# EN715_ExpansionBoard_ver1_2.net
KiCad netlist of a schematic drawn in EAGLE
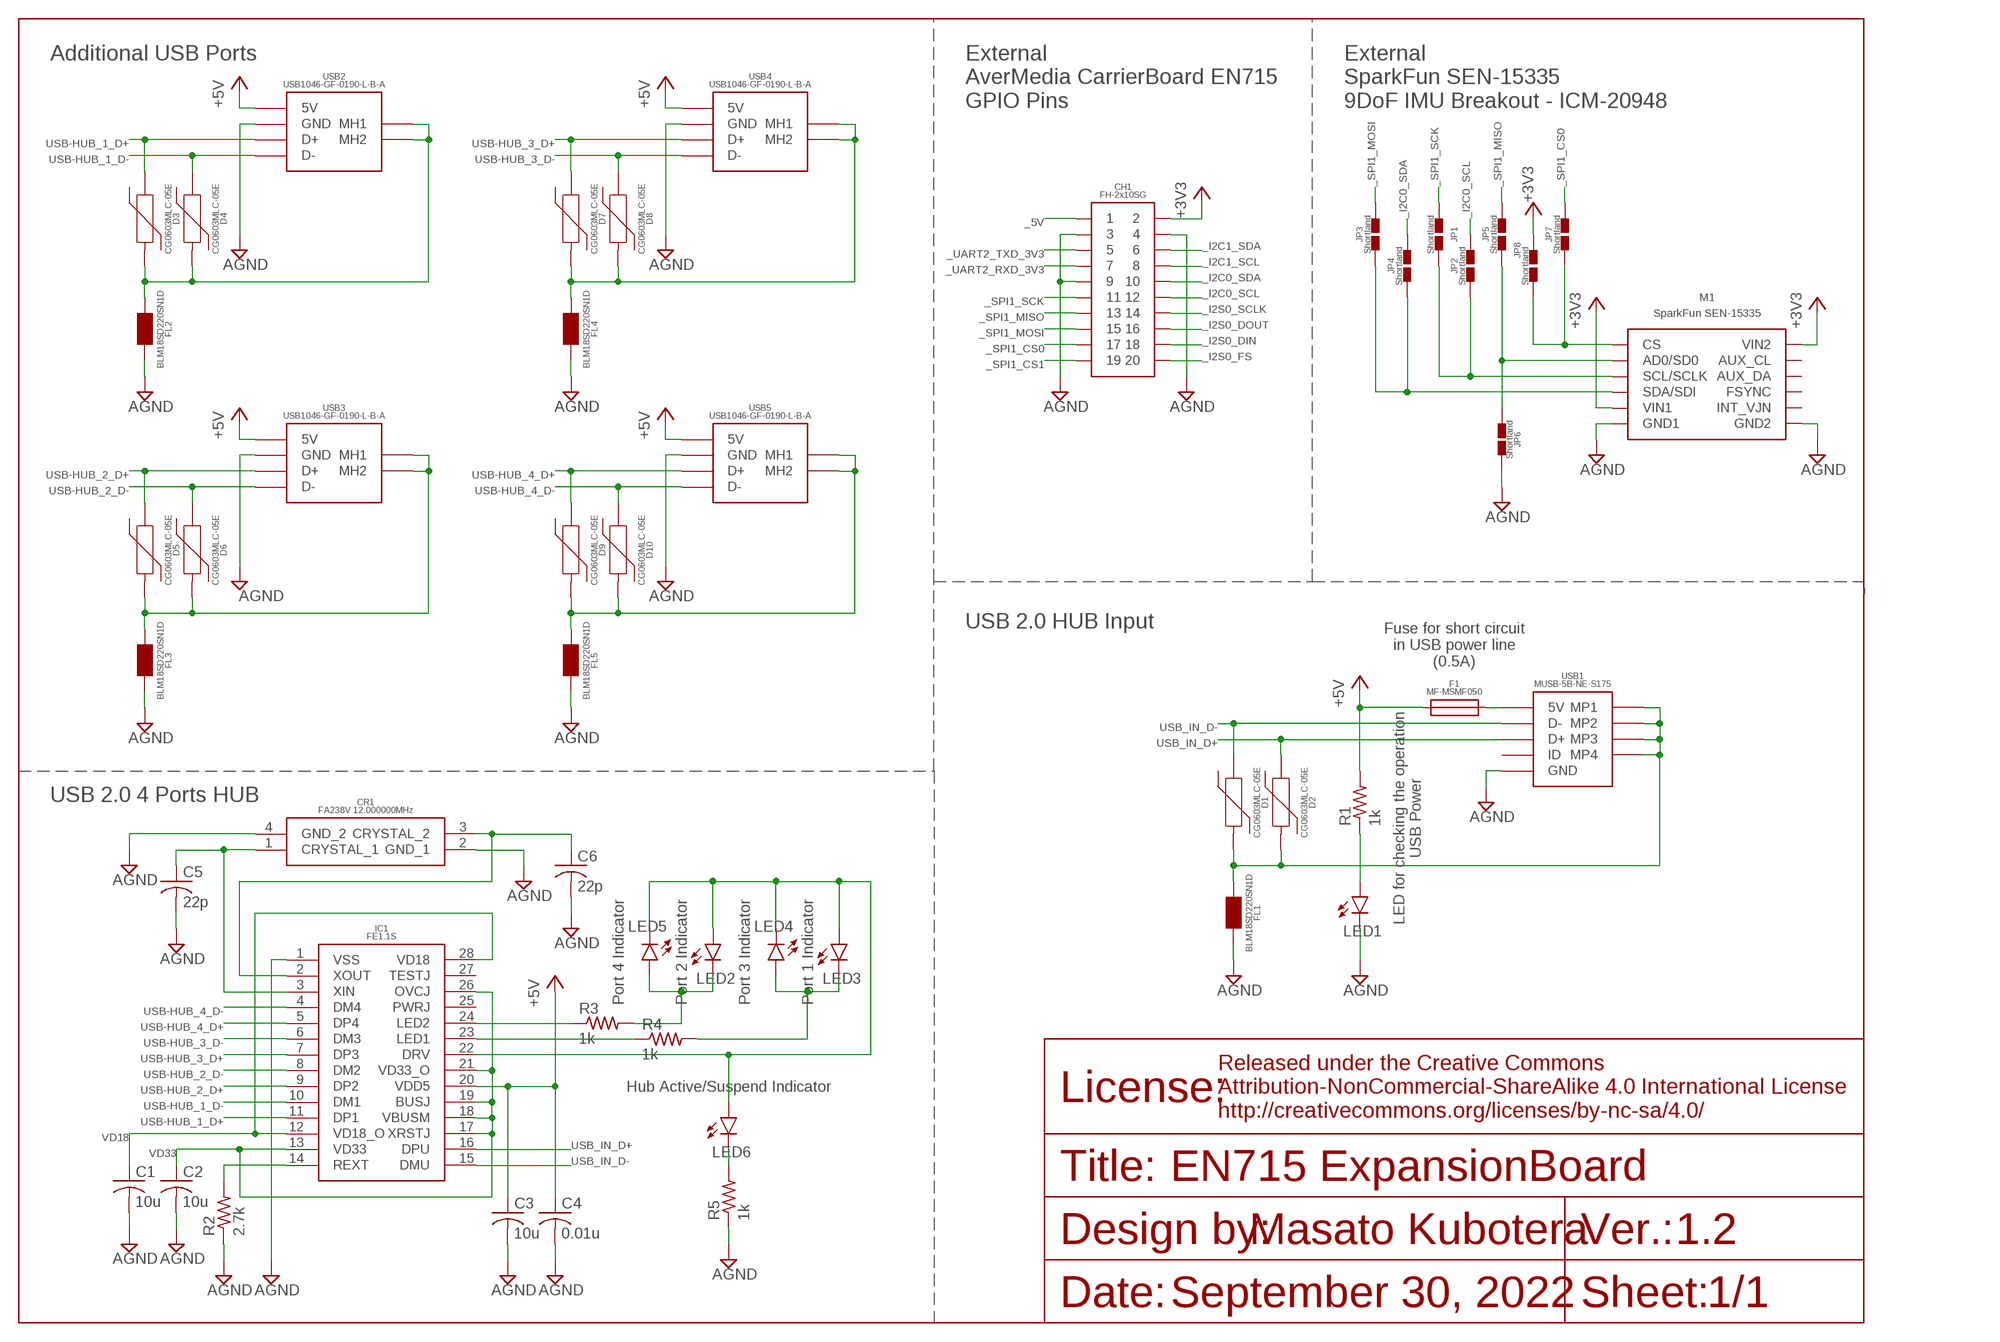
[diagram p0: schematic, sheet 1]

(export (version "E")
  (design (tool "Eeschema 10.0.6"))
  (components
    (comp (ref "C1")
      (value "10u")
      (footprint "eagle-import:C0603")
      (libsource (lib "eagle-import") (part "C-USC0603"))
    )
    (comp (ref "C2")
      (value "10u")
      (footprint "eagle-import:C0603")
      (libsource (lib "eagle-import") (part "C-USC0603"))
    )
    (comp (ref "C3")
      (value "10u")
      (footprint "eagle-import:C0603")
      (libsource (lib "eagle-import") (part "C-USC0603"))
    )
    (comp (ref "C4")
      (value "0.01u")
      (footprint "eagle-import:C0603")
      (libsource (lib "eagle-import") (part "C-USC0603"))
    )
    (comp (ref "C5")
      (value "22p")
      (footprint "eagle-import:C0603")
      (libsource (lib "eagle-import") (part "C-USC0603"))
    )
    (comp (ref "C6")
      (value "22p")
      (footprint "eagle-import:C0603")
      (libsource (lib "eagle-import") (part "C-USC0603"))
    )
    (comp (ref "CH1")
      (value "2X10")
      (footprint "eagle-import:2X10")
      (libsource (lib "eagle-import") (part "2X10"))
    )
    (comp (ref "CR1")
      (value "FA238V_12.000000MHZ")
      (footprint "eagle-import:FA238V")
      (libsource (lib "eagle-import") (part "FA238V_12.000000MHZ"))
    )
    (comp (ref "D1")
      (value "CG0603MLC-05E")
      (footprint "eagle-import:CG0603MLC-05E")
      (libsource (lib "eagle-import") (part "CG0603MLC-05E"))
    )
    (comp (ref "D2")
      (value "CG0603MLC-05E")
      (footprint "eagle-import:CG0603MLC-05E")
      (libsource (lib "eagle-import") (part "CG0603MLC-05E"))
    )
    (comp (ref "D3")
      (value "CG0603MLC-05E")
      (footprint "eagle-import:CG0603MLC-05E")
      (libsource (lib "eagle-import") (part "CG0603MLC-05E"))
    )
    (comp (ref "D4")
      (value "CG0603MLC-05E")
      (footprint "eagle-import:CG0603MLC-05E")
      (libsource (lib "eagle-import") (part "CG0603MLC-05E"))
    )
    (comp (ref "D5")
      (value "CG0603MLC-05E")
      (footprint "eagle-import:CG0603MLC-05E")
      (libsource (lib "eagle-import") (part "CG0603MLC-05E"))
    )
    (comp (ref "D6")
      (value "CG0603MLC-05E")
      (footprint "eagle-import:CG0603MLC-05E")
      (libsource (lib "eagle-import") (part "CG0603MLC-05E"))
    )
    (comp (ref "D7")
      (value "CG0603MLC-05E")
      (footprint "eagle-import:CG0603MLC-05E")
      (libsource (lib "eagle-import") (part "CG0603MLC-05E"))
    )
    (comp (ref "D8")
      (value "CG0603MLC-05E")
      (footprint "eagle-import:CG0603MLC-05E")
      (libsource (lib "eagle-import") (part "CG0603MLC-05E"))
    )
    (comp (ref "D9")
      (value "CG0603MLC-05E")
      (footprint "eagle-import:CG0603MLC-05E")
      (libsource (lib "eagle-import") (part "CG0603MLC-05E"))
    )
    (comp (ref "D10")
      (value "CG0603MLC-05E")
      (footprint "eagle-import:CG0603MLC-05E")
      (libsource (lib "eagle-import") (part "CG0603MLC-05E"))
    )
    (comp (ref "F1")
      (value "MF-MSMF050")
      (footprint "eagle-import:MF-MSMF050")
      (libsource (lib "eagle-import") (part "MF-MSMF050"))
    )
    (comp (ref "FL1")
      (value "BLM18SD220SN1D")
      (footprint "eagle-import:BLM18SD220SN1D")
      (libsource (lib "eagle-import") (part "BLM18SD220SN1D"))
    )
    (comp (ref "FL2")
      (value "BLM18SD220SN1D")
      (footprint "eagle-import:BLM18SD220SN1D")
      (libsource (lib "eagle-import") (part "BLM18SD220SN1D"))
    )
    (comp (ref "FL3")
      (value "BLM18SD220SN1D")
      (footprint "eagle-import:BLM18SD220SN1D")
      (libsource (lib "eagle-import") (part "BLM18SD220SN1D"))
    )
    (comp (ref "FL4")
      (value "BLM18SD220SN1D")
      (footprint "eagle-import:BLM18SD220SN1D")
      (libsource (lib "eagle-import") (part "BLM18SD220SN1D"))
    )
    (comp (ref "FL5")
      (value "BLM18SD220SN1D")
      (footprint "eagle-import:BLM18SD220SN1D")
      (libsource (lib "eagle-import") (part "BLM18SD220SN1D"))
    )
    (comp (ref "IC1")
      (value "FE1.1S")
      (footprint "eagle-import:FE1.1S")
      (libsource (lib "eagle-import") (part "FE1.1S"))
    )
    (comp (ref "JP1")
      (value "SHORTLAND")
      (footprint "eagle-import:SHORTLAND")
      (libsource (lib "eagle-import") (part "SHORTLAND"))
    )
    (comp (ref "JP2")
      (value "SHORTLAND")
      (footprint "eagle-import:SHORTLAND")
      (libsource (lib "eagle-import") (part "SHORTLAND"))
    )
    (comp (ref "JP3")
      (value "SHORTLAND")
      (footprint "eagle-import:SHORTLAND")
      (libsource (lib "eagle-import") (part "SHORTLAND"))
    )
    (comp (ref "JP4")
      (value "SHORTLAND")
      (footprint "eagle-import:SHORTLAND")
      (libsource (lib "eagle-import") (part "SHORTLAND"))
    )
    (comp (ref "JP5")
      (value "SHORTLAND")
      (footprint "eagle-import:SHORTLAND")
      (libsource (lib "eagle-import") (part "SHORTLAND"))
    )
    (comp (ref "JP6")
      (value "SHORTLAND")
      (footprint "eagle-import:SHORTLAND")
      (libsource (lib "eagle-import") (part "SHORTLAND"))
    )
    (comp (ref "JP7")
      (value "SHORTLAND")
      (footprint "eagle-import:SHORTLAND")
      (libsource (lib "eagle-import") (part "SHORTLAND"))
    )
    (comp (ref "JP8")
      (value "SHORTLAND")
      (footprint "eagle-import:SHORTLAND")
      (libsource (lib "eagle-import") (part "SHORTLAND"))
    )
    (comp (ref "LED1")
      (value "LEDSML0603")
      (footprint "eagle-import:SML0603")
      (libsource (lib "eagle-import") (part "LEDSML0603"))
    )
    (comp (ref "LED2")
      (value "LEDSML0603")
      (footprint "eagle-import:SML0603")
      (libsource (lib "eagle-import") (part "LEDSML0603"))
    )
    (comp (ref "LED3")
      (value "LEDSML0603")
      (footprint "eagle-import:SML0603")
      (libsource (lib "eagle-import") (part "LEDSML0603"))
    )
    (comp (ref "LED4")
      (value "LEDSML0603")
      (footprint "eagle-import:SML0603")
      (libsource (lib "eagle-import") (part "LEDSML0603"))
    )
    (comp (ref "LED5")
      (value "LEDSML0603")
      (footprint "eagle-import:SML0603")
      (libsource (lib "eagle-import") (part "LEDSML0603"))
    )
    (comp (ref "LED6")
      (value "LEDSML0603")
      (footprint "eagle-import:SML0603")
      (libsource (lib "eagle-import") (part "LEDSML0603"))
    )
    (comp (ref "M1")
      (value "SPARKFUN_SEN-15335")
      (footprint "eagle-import:SPARKFUN_SEN-15335")
      (libsource (lib "eagle-import") (part "SPARKFUN_SEN-15335"))
    )
    (comp (ref "R1")
      (value "1k")
      (footprint "eagle-import:R0603")
      (libsource (lib "eagle-import") (part "R-US_R0603"))
    )
    (comp (ref "R2")
      (value "2.7k")
      (footprint "eagle-import:R0603")
      (libsource (lib "eagle-import") (part "R-US_R0603"))
    )
    (comp (ref "R3")
      (value "1k")
      (footprint "eagle-import:R0603")
      (libsource (lib "eagle-import") (part "R-US_R0603"))
    )
    (comp (ref "R4")
      (value "1k")
      (footprint "eagle-import:R0603")
      (libsource (lib "eagle-import") (part "R-US_R0603"))
    )
    (comp (ref "R5")
      (value "1k")
      (footprint "eagle-import:R0603")
      (libsource (lib "eagle-import") (part "R-US_R0603"))
    )
    (comp (ref "USB1")
      (value "MINI_USB_B_SMD")
      (footprint "eagle-import:MINI_USB_B_SMD")
      (libsource (lib "eagle-import") (part "MINI_USB_B_SMD"))
    )
    (comp (ref "USB2")
      (value "USB_A_X1_SMD")
      (footprint "eagle-import:USB_A_X1_SMD")
      (libsource (lib "eagle-import") (part "USB_A_X1_SMD"))
    )
    (comp (ref "USB3")
      (value "USB_A_X1_SMD")
      (footprint "eagle-import:USB_A_X1_SMD")
      (libsource (lib "eagle-import") (part "USB_A_X1_SMD"))
    )
    (comp (ref "USB4")
      (value "USB_A_X1_SMD")
      (footprint "eagle-import:USB_A_X1_SMD")
      (libsource (lib "eagle-import") (part "USB_A_X1_SMD"))
    )
    (comp (ref "USB5")
      (value "USB_A_X1_SMD")
      (footprint "eagle-import:USB_A_X1_SMD")
      (libsource (lib "eagle-import") (part "USB_A_X1_SMD"))
    )
  )
  (nets
    (net (code "1") (name "+3V3") (class "Default")
      (node (ref "CH1") (pin "2") (pinfunction "2_2") (pintype "bidirectional"))
      (node (ref "JP8") (pin "2") (pinfunction "2_2") (pintype "bidirectional"))
      (node (ref "M1") (pin "VIN") (pinfunction "VIN1_VIN") (pintype "bidirectional"))
      (node (ref "M1") (pin "VIN1") (pinfunction "VIN2_VIN1") (pintype "bidirectional"))
    )
    (net (code "2") (name "+5V") (class "Default")
      (node (ref "C3") (pin "1") (pinfunction "1_1") (pintype "passive"))
      (node (ref "C4") (pin "1") (pinfunction "1_1") (pintype "passive"))
      (node (ref "F1") (pin "1") (pinfunction "1_1") (pintype "bidirectional"))
      (node (ref "IC1") (pin "20") (pinfunction "VDD5_20") (pintype "bidirectional"))
      (node (ref "R1") (pin "2") (pinfunction "2_2") (pintype "passive"))
      (node (ref "USB2") (pin "1") (pinfunction "5V_1") (pintype "bidirectional"))
      (node (ref "USB3") (pin "1") (pinfunction "5V_1") (pintype "bidirectional"))
      (node (ref "USB4") (pin "1") (pinfunction "5V_1") (pintype "bidirectional"))
      (node (ref "USB5") (pin "1") (pinfunction "5V_1") (pintype "bidirectional"))
    )
    (net (code "3") (name "/USB-HUB_1_D+") (class "Default")
      (node (ref "D3") (pin "1") (pinfunction "1_1") (pintype "bidirectional"))
      (node (ref "IC1") (pin "11") (pinfunction "DP1_11") (pintype "bidirectional"))
      (node (ref "USB2") (pin "3") (pinfunction "D+_3") (pintype "bidirectional"))
    )
    (net (code "4") (name "/USB-HUB_1_D-") (class "Default")
      (node (ref "D4") (pin "1") (pinfunction "1_1") (pintype "bidirectional"))
      (node (ref "IC1") (pin "10") (pinfunction "DM1_10") (pintype "bidirectional"))
      (node (ref "USB2") (pin "2") (pinfunction "D-_2") (pintype "bidirectional"))
    )
    (net (code "5") (name "/USB-HUB_2_D+") (class "Default")
      (node (ref "D5") (pin "1") (pinfunction "1_1") (pintype "bidirectional"))
      (node (ref "IC1") (pin "9") (pinfunction "DP2_9") (pintype "bidirectional"))
      (node (ref "USB3") (pin "3") (pinfunction "D+_3") (pintype "bidirectional"))
    )
    (net (code "6") (name "/USB-HUB_2_D-") (class "Default")
      (node (ref "D6") (pin "1") (pinfunction "1_1") (pintype "bidirectional"))
      (node (ref "IC1") (pin "8") (pinfunction "DM2_8") (pintype "bidirectional"))
      (node (ref "USB3") (pin "2") (pinfunction "D-_2") (pintype "bidirectional"))
    )
    (net (code "7") (name "/USB-HUB_3_D+") (class "Default")
      (node (ref "D7") (pin "1") (pinfunction "1_1") (pintype "bidirectional"))
      (node (ref "IC1") (pin "7") (pinfunction "DP3_7") (pintype "bidirectional"))
      (node (ref "USB4") (pin "3") (pinfunction "D+_3") (pintype "bidirectional"))
    )
    (net (code "8") (name "/USB-HUB_3_D-") (class "Default")
      (node (ref "D8") (pin "1") (pinfunction "1_1") (pintype "bidirectional"))
      (node (ref "IC1") (pin "6") (pinfunction "DM3_6") (pintype "bidirectional"))
      (node (ref "USB4") (pin "2") (pinfunction "D-_2") (pintype "bidirectional"))
    )
    (net (code "9") (name "/USB-HUB_4_D+") (class "Default")
      (node (ref "D9") (pin "1") (pinfunction "1_1") (pintype "bidirectional"))
      (node (ref "IC1") (pin "5") (pinfunction "DP4_5") (pintype "bidirectional"))
      (node (ref "USB5") (pin "3") (pinfunction "D+_3") (pintype "bidirectional"))
    )
    (net (code "10") (name "/USB-HUB_4_D-") (class "Default")
      (node (ref "D10") (pin "1") (pinfunction "1_1") (pintype "bidirectional"))
      (node (ref "IC1") (pin "4") (pinfunction "DM4_4") (pintype "bidirectional"))
      (node (ref "USB5") (pin "2") (pinfunction "D-_2") (pintype "bidirectional"))
    )
    (net (code "11") (name "/USB_IN_D+") (class "Default")
      (node (ref "D2") (pin "1") (pinfunction "1_1") (pintype "bidirectional"))
      (node (ref "IC1") (pin "16") (pinfunction "DPU_16") (pintype "bidirectional"))
      (node (ref "USB1") (pin "3") (pinfunction "D+_3") (pintype "bidirectional"))
    )
    (net (code "12") (name "/USB_IN_D-") (class "Default")
      (node (ref "D1") (pin "1") (pinfunction "1_1") (pintype "bidirectional"))
      (node (ref "IC1") (pin "15") (pinfunction "DMU_15") (pintype "bidirectional"))
      (node (ref "USB1") (pin "2") (pinfunction "D-_2") (pintype "bidirectional"))
    )
    (net (code "13") (name "/VD18") (class "Default")
      (node (ref "C1") (pin "1") (pinfunction "1_1") (pintype "passive"))
      (node (ref "IC1") (pin "12") (pinfunction "VD18_O_12") (pintype "bidirectional"))
      (node (ref "IC1") (pin "28") (pinfunction "VD18_28") (pintype "bidirectional"))
    )
    (net (code "14") (name "/VD33") (class "Default")
      (node (ref "C2") (pin "1") (pinfunction "1_1") (pintype "passive"))
      (node (ref "IC1") (pin "13") (pinfunction "VD33_13") (pintype "bidirectional"))
      (node (ref "IC1") (pin "17") (pinfunction "XRSTJ_17") (pintype "bidirectional"))
      (node (ref "IC1") (pin "18") (pinfunction "VBUSM_18") (pintype "bidirectional"))
      (node (ref "IC1") (pin "19") (pinfunction "BUSJ_19") (pintype "bidirectional"))
      (node (ref "IC1") (pin "21") (pinfunction "VD33_O_21") (pintype "bidirectional"))
      (node (ref "IC1") (pin "26") (pinfunction "OVCJ_26") (pintype "bidirectional"))
    )
    (net (code "15") (name "/_5V") (class "Default")
      (node (ref "CH1") (pin "1") (pinfunction "1_1") (pintype "bidirectional"))
    )
    (net (code "16") (name "/_I2C0_SCL") (class "Default")
      (node (ref "CH1") (pin "12") (pinfunction "12_12") (pintype "bidirectional"))
      (node (ref "JP2") (pin "2") (pinfunction "2_2") (pintype "bidirectional"))
    )
    (net (code "17") (name "/_I2C0_SDA") (class "Default")
      (node (ref "CH1") (pin "10") (pinfunction "10_10") (pintype "bidirectional"))
      (node (ref "JP4") (pin "2") (pinfunction "2_2") (pintype "bidirectional"))
    )
    (net (code "18") (name "/_I2C1_SCL") (class "Default")
      (node (ref "CH1") (pin "8") (pinfunction "8_8") (pintype "bidirectional"))
    )
    (net (code "19") (name "/_I2C1_SDA") (class "Default")
      (node (ref "CH1") (pin "6") (pinfunction "6_6") (pintype "bidirectional"))
    )
    (net (code "20") (name "/_I2S0_DIN") (class "Default")
      (node (ref "CH1") (pin "18") (pinfunction "18_18") (pintype "bidirectional"))
    )
    (net (code "21") (name "/_I2S0_DOUT") (class "Default")
      (node (ref "CH1") (pin "16") (pinfunction "16_16") (pintype "bidirectional"))
    )
    (net (code "22") (name "/_I2S0_FS") (class "Default")
      (node (ref "CH1") (pin "20") (pinfunction "20_20") (pintype "bidirectional"))
    )
    (net (code "23") (name "/_I2S0_SCLK") (class "Default")
      (node (ref "CH1") (pin "14") (pinfunction "14_14") (pintype "bidirectional"))
    )
    (net (code "24") (name "/_SPI1_CS0") (class "Default")
      (node (ref "CH1") (pin "17") (pinfunction "17_17") (pintype "bidirectional"))
      (node (ref "JP7") (pin "2") (pinfunction "2_2") (pintype "bidirectional"))
    )
    (net (code "25") (name "/_SPI1_CS1") (class "Default")
      (node (ref "CH1") (pin "19") (pinfunction "19_19") (pintype "bidirectional"))
    )
    (net (code "26") (name "/_SPI1_MISO") (class "Default")
      (node (ref "CH1") (pin "13") (pinfunction "13_13") (pintype "bidirectional"))
      (node (ref "JP5") (pin "2") (pinfunction "2_2") (pintype "bidirectional"))
    )
    (net (code "27") (name "/_SPI1_MOSI") (class "Default")
      (node (ref "CH1") (pin "15") (pinfunction "15_15") (pintype "bidirectional"))
      (node (ref "JP3") (pin "2") (pinfunction "2_2") (pintype "bidirectional"))
    )
    (net (code "28") (name "/_SPI1_SCK") (class "Default")
      (node (ref "CH1") (pin "11") (pinfunction "11_11") (pintype "bidirectional"))
      (node (ref "JP1") (pin "2") (pinfunction "2_2") (pintype "bidirectional"))
    )
    (net (code "29") (name "/_UART2_RXD_3V3") (class "Default")
      (node (ref "CH1") (pin "7") (pinfunction "7_7") (pintype "bidirectional"))
    )
    (net (code "30") (name "/_UART2_TXD_3V3") (class "Default")
      (node (ref "CH1") (pin "5") (pinfunction "5_5") (pintype "bidirectional"))
    )
    (net (code "31") (name "AGND") (class "Default")
      (node (ref "C1") (pin "2") (pinfunction "2_2") (pintype "passive"))
      (node (ref "C2") (pin "2") (pinfunction "2_2") (pintype "passive"))
      (node (ref "C3") (pin "2") (pinfunction "2_2") (pintype "passive"))
      (node (ref "C4") (pin "2") (pinfunction "2_2") (pintype "passive"))
      (node (ref "C5") (pin "2") (pinfunction "2_2") (pintype "passive"))
      (node (ref "C6") (pin "2") (pinfunction "2_2") (pintype "passive"))
      (node (ref "CH1") (pin "3") (pinfunction "3_3") (pintype "bidirectional"))
      (node (ref "CH1") (pin "4") (pinfunction "4_4") (pintype "bidirectional"))
      (node (ref "CH1") (pin "9") (pinfunction "9_9") (pintype "bidirectional"))
      (node (ref "CR1") (pin "2") (pinfunction "GND_1_2") (pintype "bidirectional"))
      (node (ref "CR1") (pin "4") (pinfunction "GND_2_4") (pintype "bidirectional"))
      (node (ref "FL1") (pin "2") (pinfunction "2_2") (pintype "bidirectional"))
      (node (ref "FL2") (pin "2") (pinfunction "2_2") (pintype "bidirectional"))
      (node (ref "FL3") (pin "2") (pinfunction "2_2") (pintype "bidirectional"))
      (node (ref "FL4") (pin "2") (pinfunction "2_2") (pintype "bidirectional"))
      (node (ref "FL5") (pin "2") (pinfunction "2_2") (pintype "bidirectional"))
      (node (ref "IC1") (pin "1") (pinfunction "VSS_1") (pintype "bidirectional"))
      (node (ref "JP6") (pin "2") (pinfunction "2_2") (pintype "bidirectional"))
      (node (ref "LED1") (pin "C") (pinfunction "C_C") (pintype "passive"))
      (node (ref "M1") (pin "GND1") (pinfunction "GND1_GND1") (pintype "bidirectional"))
      (node (ref "M1") (pin "GND2") (pinfunction "GND2_GND2") (pintype "bidirectional"))
      (node (ref "R2") (pin "1") (pinfunction "1_1") (pintype "passive"))
      (node (ref "R5") (pin "1") (pinfunction "1_1") (pintype "passive"))
      (node (ref "USB1") (pin "5") (pinfunction "GND_5") (pintype "bidirectional"))
      (node (ref "USB2") (pin "4") (pinfunction "GND_4") (pintype "bidirectional"))
      (node (ref "USB3") (pin "4") (pinfunction "GND_4") (pintype "bidirectional"))
      (node (ref "USB4") (pin "4") (pinfunction "GND_4") (pintype "bidirectional"))
      (node (ref "USB5") (pin "4") (pinfunction "GND_4") (pintype "bidirectional"))
    )
    (net (code "32") (name "Net-(CR1-CRYSTAL_1)") (class "Default")
      (node (ref "C5") (pin "1") (pinfunction "1_1") (pintype "passive"))
      (node (ref "CR1") (pin "1") (pinfunction "CRYSTAL_1_1") (pintype "bidirectional"))
      (node (ref "IC1") (pin "3") (pinfunction "XIN_3") (pintype "bidirectional"))
    )
    (net (code "33") (name "Net-(CR1-CRYSTAL_2)") (class "Default")
      (node (ref "C6") (pin "1") (pinfunction "1_1") (pintype "passive"))
      (node (ref "CR1") (pin "3") (pinfunction "CRYSTAL_2_3") (pintype "bidirectional"))
      (node (ref "IC1") (pin "2") (pinfunction "XOUT_2") (pintype "bidirectional"))
    )
    (net (code "34") (name "Net-(D1-Pad2)") (class "Default")
      (node (ref "D1") (pin "2") (pinfunction "2_2") (pintype "bidirectional"))
      (node (ref "D2") (pin "2") (pinfunction "2_2") (pintype "bidirectional"))
      (node (ref "FL1") (pin "1") (pinfunction "1_1") (pintype "bidirectional"))
      (node (ref "USB1") (pin "MP1") (pinfunction "MP1_MP1") (pintype "bidirectional"))
      (node (ref "USB1") (pin "MP2") (pinfunction "MP2_MP2") (pintype "bidirectional"))
      (node (ref "USB1") (pin "MP3") (pinfunction "MP3_MP3") (pintype "bidirectional"))
      (node (ref "USB1") (pin "MP4") (pinfunction "MP4_MP4") (pintype "bidirectional"))
    )
    (net (code "35") (name "Net-(D3-Pad2)") (class "Default")
      (node (ref "D3") (pin "2") (pinfunction "2_2") (pintype "bidirectional"))
      (node (ref "D4") (pin "2") (pinfunction "2_2") (pintype "bidirectional"))
      (node (ref "FL2") (pin "1") (pinfunction "1_1") (pintype "bidirectional"))
      (node (ref "USB2") (pin "MH1") (pinfunction "MH1_MH1") (pintype "bidirectional"))
      (node (ref "USB2") (pin "MH2") (pinfunction "MH2_MH2") (pintype "bidirectional"))
    )
    (net (code "36") (name "Net-(D5-Pad2)") (class "Default")
      (node (ref "D5") (pin "2") (pinfunction "2_2") (pintype "bidirectional"))
      (node (ref "D6") (pin "2") (pinfunction "2_2") (pintype "bidirectional"))
      (node (ref "FL3") (pin "1") (pinfunction "1_1") (pintype "bidirectional"))
      (node (ref "USB3") (pin "MH1") (pinfunction "MH1_MH1") (pintype "bidirectional"))
      (node (ref "USB3") (pin "MH2") (pinfunction "MH2_MH2") (pintype "bidirectional"))
    )
    (net (code "37") (name "Net-(D7-Pad2)") (class "Default")
      (node (ref "D7") (pin "2") (pinfunction "2_2") (pintype "bidirectional"))
      (node (ref "D8") (pin "2") (pinfunction "2_2") (pintype "bidirectional"))
      (node (ref "FL4") (pin "1") (pinfunction "1_1") (pintype "bidirectional"))
      (node (ref "USB4") (pin "MH1") (pinfunction "MH1_MH1") (pintype "bidirectional"))
      (node (ref "USB4") (pin "MH2") (pinfunction "MH2_MH2") (pintype "bidirectional"))
    )
    (net (code "38") (name "Net-(D10-Pad2)") (class "Default")
      (node (ref "D10") (pin "2") (pinfunction "2_2") (pintype "bidirectional"))
      (node (ref "D9") (pin "2") (pinfunction "2_2") (pintype "bidirectional"))
      (node (ref "FL5") (pin "1") (pinfunction "1_1") (pintype "bidirectional"))
      (node (ref "USB5") (pin "MH1") (pinfunction "MH1_MH1") (pintype "bidirectional"))
      (node (ref "USB5") (pin "MH2") (pinfunction "MH2_MH2") (pintype "bidirectional"))
    )
    (net (code "39") (name "Net-(IC1-DRV)") (class "Default")
      (node (ref "IC1") (pin "22") (pinfunction "DRV_22") (pintype "bidirectional"))
      (node (ref "LED2") (pin "A") (pinfunction "A_A") (pintype "passive"))
      (node (ref "LED3") (pin "A") (pinfunction "A_A") (pintype "passive"))
      (node (ref "LED4") (pin "C") (pinfunction "C_C") (pintype "passive"))
      (node (ref "LED5") (pin "C") (pinfunction "C_C") (pintype "passive"))
      (node (ref "LED6") (pin "A") (pinfunction "A_A") (pintype "passive"))
    )
    (net (code "40") (name "Net-(IC1-LED1)") (class "Default")
      (node (ref "IC1") (pin "23") (pinfunction "LED1_23") (pintype "bidirectional"))
      (node (ref "R4") (pin "1") (pinfunction "1_1") (pintype "passive"))
    )
    (net (code "41") (name "Net-(IC1-LED2)") (class "Default")
      (node (ref "IC1") (pin "24") (pinfunction "LED2_24") (pintype "bidirectional"))
      (node (ref "R3") (pin "1") (pinfunction "1_1") (pintype "passive"))
    )
    (net (code "42") (name "Net-(IC1-REXT)") (class "Default")
      (node (ref "IC1") (pin "14") (pinfunction "REXT_14") (pintype "bidirectional"))
      (node (ref "R2") (pin "2") (pinfunction "2_2") (pintype "passive"))
    )
    (net (code "43") (name "Net-(JP1-Pad1)") (class "Default")
      (node (ref "JP1") (pin "1") (pinfunction "1_1") (pintype "bidirectional"))
      (node (ref "JP2") (pin "1") (pinfunction "1_1") (pintype "bidirectional"))
      (node (ref "M1") (pin "SCL/SCLK") (pinfunction "SCL/SCLK_SCL/SCLK") (pintype "bidirectional"))
    )
    (net (code "44") (name "Net-(JP3-Pad1)") (class "Default")
      (node (ref "JP3") (pin "1") (pinfunction "1_1") (pintype "bidirectional"))
      (node (ref "JP4") (pin "1") (pinfunction "1_1") (pintype "bidirectional"))
      (node (ref "M1") (pin "SDA/SDI") (pinfunction "SDA/SDI_SDA/SDI") (pintype "bidirectional"))
    )
    (net (code "45") (name "Net-(JP5-Pad1)") (class "Default")
      (node (ref "JP5") (pin "1") (pinfunction "1_1") (pintype "bidirectional"))
      (node (ref "JP6") (pin "1") (pinfunction "1_1") (pintype "bidirectional"))
      (node (ref "M1") (pin "AD0/SD0") (pinfunction "AD0/SD0_AD0/SD0") (pintype "bidirectional"))
    )
    (net (code "46") (name "Net-(JP7-Pad1)") (class "Default")
      (node (ref "JP7") (pin "1") (pinfunction "1_1") (pintype "bidirectional"))
      (node (ref "JP8") (pin "1") (pinfunction "1_1") (pintype "bidirectional"))
      (node (ref "M1") (pin "CS") (pinfunction "CS_CS") (pintype "bidirectional"))
    )
    (net (code "47") (name "Net-(LED1-PadA)") (class "Default")
      (node (ref "LED1") (pin "A") (pinfunction "A_A") (pintype "passive"))
      (node (ref "R1") (pin "1") (pinfunction "1_1") (pintype "passive"))
    )
    (net (code "48") (name "Net-(LED2-PadC)") (class "Default")
      (node (ref "LED2") (pin "C") (pinfunction "C_C") (pintype "passive"))
      (node (ref "LED5") (pin "A") (pinfunction "A_A") (pintype "passive"))
      (node (ref "R3") (pin "2") (pinfunction "2_2") (pintype "passive"))
    )
    (net (code "49") (name "Net-(LED3-PadC)") (class "Default")
      (node (ref "LED3") (pin "C") (pinfunction "C_C") (pintype "passive"))
      (node (ref "LED4") (pin "A") (pinfunction "A_A") (pintype "passive"))
      (node (ref "R4") (pin "2") (pinfunction "2_2") (pintype "passive"))
    )
    (net (code "50") (name "Net-(LED6-PadC)") (class "Default")
      (node (ref "LED6") (pin "C") (pinfunction "C_C") (pintype "passive"))
      (node (ref "R5") (pin "2") (pinfunction "2_2") (pintype "passive"))
    )
    (net (code "51") (name "Net-(USB1-5V)") (class "Default")
      (node (ref "F1") (pin "2") (pinfunction "2_2") (pintype "bidirectional"))
      (node (ref "USB1") (pin "1") (pinfunction "5V_1") (pintype "bidirectional"))
    )
    (net (code "52") (name "unconnected-(IC1-PWRJ-Pad25)") (class "Default")
      (node (ref "IC1") (pin "25") (pinfunction "PWRJ_25") (pintype "bidirectional"))
    )
    (net (code "53") (name "unconnected-(IC1-TESTJ-Pad27)") (class "Default")
      (node (ref "IC1") (pin "27") (pinfunction "TESTJ_27") (pintype "bidirectional"))
    )
    (net (code "54") (name "unconnected-(M1-PadAUX_CL)") (class "Default")
      (node (ref "M1") (pin "AUX_CL") (pinfunction "AUX_CL_AUX_CL") (pintype "bidirectional"))
    )
    (net (code "55") (name "unconnected-(M1-PadAUX_DA)") (class "Default")
      (node (ref "M1") (pin "AUX_DA") (pinfunction "AUX_DA_AUX_DA") (pintype "bidirectional"))
    )
    (net (code "56") (name "unconnected-(M1-PadFSYNC)") (class "Default")
      (node (ref "M1") (pin "FSYNC") (pinfunction "FSYNC_FSYNC") (pintype "bidirectional"))
    )
    (net (code "57") (name "unconnected-(M1-PadINT_VJN)") (class "Default")
      (node (ref "M1") (pin "INT_VJN") (pinfunction "INT_VJN_INT_VJN") (pintype "bidirectional"))
    )
    (net (code "58") (name "unconnected-(USB1-ID-Pad4)") (class "Default")
      (node (ref "USB1") (pin "4") (pinfunction "ID_4") (pintype "bidirectional"))
    )
  )
)
